# MSP430FR5739.net
KiCad netlist of a schematic drawn in Altium Designer
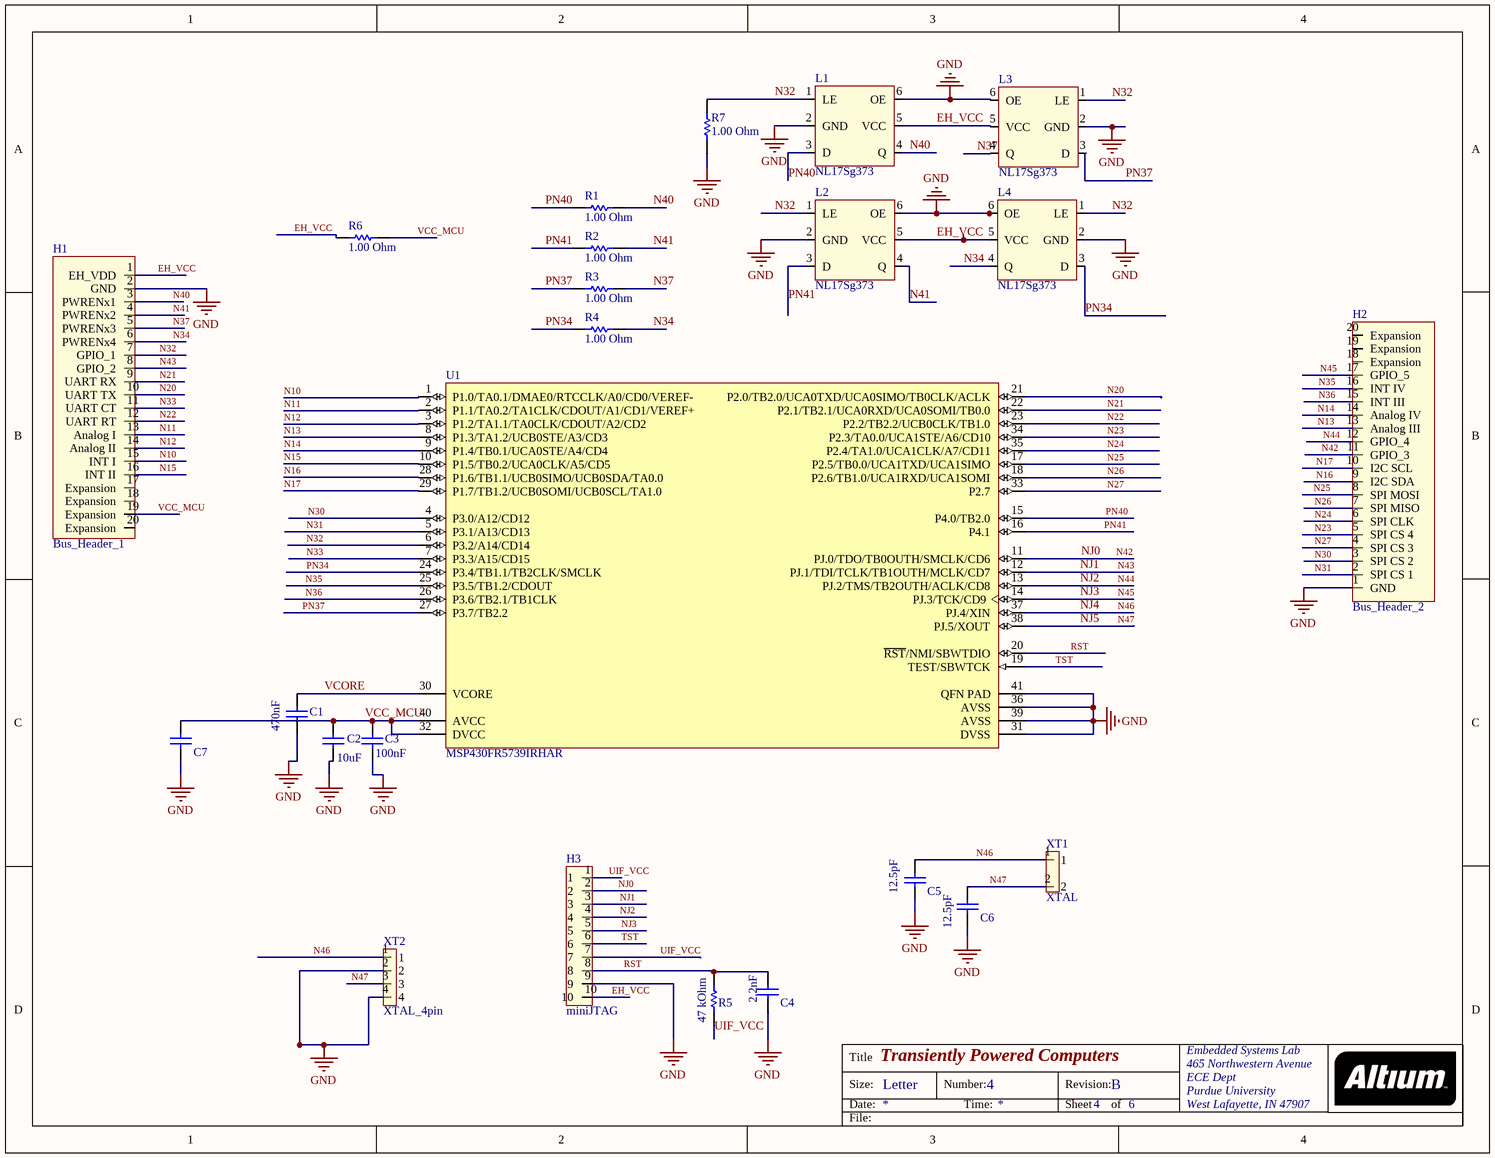
[diagram p0: MSP430FR5739.SchDoc]

(export (version "E")
  (design (tool "Eeschema 10.0.6"))
  (components
    (comp (ref "C1")
      (value "470nF")
      (footprint "CAPC0201(0603)33_N")
      (description "CAP 220nF 4V ±20% 0201 (0603 Metric) Thickness 0.33mm SMD")
      (fields (field (name "TOLERANCE") "±20%") (field (name "Comment") "CAP 220nF 4V 0201(0603)"))
      (libsource (lib "Altium Content Vault") (part "CAP"))
    )
    (comp (ref "C2")
      (value "10uF")
      (footprint "CAPC0402(1005)70_N")
      (description "CAP 10uF 4V ±20% 0402 (1005 Metric) Thickness 0.7mm SMD")
      (fields (field (name "TOLERANCE") "±20%") (field (name "Comment") "CAP 4.7uF 4V 0402(1005)"))
      (libsource (lib "Altium Content Vault") (part "CAP"))
    )
    (comp (ref "C3")
      (value "100nF")
      (footprint "CAPC0201(0603)33_M")
      (description "CAP 100nF 4V ±10% 0201 (0603 Metric) Thickness 0.33mm SMD")
      (fields (field (name "TOLERANCE") "±10%") (field (name "Comment") "CAP 100nF 4V 0201(0603)"))
      (libsource (lib "Altium Content Vault") (part "CMP-1033-00657-1"))
    )
    (comp (ref "C4")
      (value "2.2nF")
      (footprint "CAPC0402(1005)60_M")
      (description "CAP 2.2uF 4V ±20% 0402 (1005 Metric) Thickness 0.6mm SMD")
      (fields (field (name "TOLERANCE") "±20%") (field (name "Comment") "CAP 2.2uF 4V 0402(1005)"))
      (libsource (lib "Altium Content Vault") (part "CMP-1034-02124-1"))
    )
    (comp (ref "C5")
      (value "12.5pF")
      (footprint "CAPC0402(1005)60_N")
      (description "CAP 470nF 4V ±10% 0402 (1005 Metric) Thickness 0.6mm SMD")
      (fields (field (name "TOLERANCE") "±10%") (field (name "Comment") "CAP 470nF 4V 0402(1005)"))
      (libsource (lib "Altium Content Vault") (part "CMP-1034-02101-1"))
    )
    (comp (ref "C6")
      (value "12.5pF")
      (footprint "CAPC0402(1005)60_N")
      (description "CAP 470nF 4V ±10% 0402 (1005 Metric) Thickness 0.6mm SMD")
      (fields (field (name "TOLERANCE") "±10%") (field (name "Comment") "CAP 470nF 4V 0402(1005)"))
      (libsource (lib "Altium Content Vault") (part "CMP-1034-02101-1"))
    )
    (comp (ref "C7")
      (value "CAP 0.5pF 10V 0805(2012)")
      (footprint "CAPC0805(2012)75_N")
      (description "CAP 0.5pF 10V ±0.1pF 0805 (2012 Metric) Thickness 0.75mm SMD")
      (fields (field (name "TOLERANCE") "±0.1pF"))
      (libsource (lib "Altium Content Vault") (part "CMP-1036-00001-1"))
    )
    (comp (ref "H1")
      (value "Bus_Header_1")
      (footprint "Male Single row 20 pin header")
      (libsource (lib "Basic_components_hrishi") (part "Bus_Header_1"))
    )
    (comp (ref "H2")
      (value "Bus_Header_2")
      (footprint "Male Single row 20 pin header")
      (libsource (lib "Basic_components_hrishi") (part "Bus_Header_2"))
    )
    (comp (ref "H3")
      (value "miniJTAG")
      (footprint "SMT10pin_micro")
      (libsource (lib "Basic_components_hrishi") (part "miniJTAG"))
    )
    (comp (ref "L1")
      (value "NL17Sg373")
      (footprint "SOT65P210X110-6N")
      (libsource (lib "") (part "NL17Sg373_1"))
    )
    (comp (ref "L2")
      (value "NL17Sg373")
      (footprint "SOT65P210X110-6N")
      (libsource (lib "") (part "NL17Sg373_1"))
    )
    (comp (ref "L3")
      (value "NL17Sg373")
      (footprint "SOT65P210X110-6N")
      (libsource (lib "Basic_components_hrishi") (part "NL17Sg373"))
    )
    (comp (ref "L4")
      (value "NL17Sg373")
      (footprint "SOT65P210X110-6N")
      (libsource (lib "Basic_components_hrishi") (part "NL17Sg373"))
    )
    (comp (ref "R1")
      (value "1.00 Ohm")
      (footprint "RESC0402(1005)_N")
      (description "1R 0.063W 5% 0402 (1005 Metric)  SMD")
      (fields (field (name "POWER") "0.063 W") (field (name "TOLERANCE") "5 %"))
      (libsource (lib "Altium Content Vault") (part "CMP-1011-00002-1"))
    )
    (comp (ref "R2")
      (value "1.00 Ohm")
      (footprint "RESC0402(1005)_N")
      (description "1R 0.063W 5% 0402 (1005 Metric)  SMD")
      (fields (field (name "POWER") "0.063 W") (field (name "TOLERANCE") "5 %"))
      (libsource (lib "Altium Content Vault") (part "CMP-1011-00002-1"))
    )
    (comp (ref "R3")
      (value "1.00 Ohm")
      (footprint "RESC0402(1005)_N")
      (description "1R 0.063W 5% 0402 (1005 Metric)  SMD")
      (fields (field (name "POWER") "0.063 W") (field (name "TOLERANCE") "5 %"))
      (libsource (lib "Altium Content Vault") (part "CMP-1011-00002-1"))
    )
    (comp (ref "R4")
      (value "1.00 Ohm")
      (footprint "RESC0402(1005)_N")
      (description "1R 0.063W 5% 0402 (1005 Metric)  SMD")
      (fields (field (name "POWER") "0.063 W") (field (name "TOLERANCE") "5 %"))
      (libsource (lib "Altium Content Vault") (part "CMP-1011-00002-1"))
    )
    (comp (ref "R5")
      (value "47 kOhm")
      (footprint "RESC0402(1005)_M")
      (description "47K 0.063W 5% 0402 (1005 Metric)  SMD")
      (fields (field (name "TOLERANCE") "5 %") (field (name "POWER") "0.063 W"))
      (libsource (lib "Altium Content Vault") (part "CMP-1011-00114-1"))
    )
    (comp (ref "R6")
      (value "1.00 Ohm")
      (footprint "RESC0402(1005)_N")
      (description "1R 0.063W 5% 0402 (1005 Metric)  SMD")
      (fields (field (name "POWER") "0.063 W") (field (name "TOLERANCE") "5 %"))
      (libsource (lib "Altium Content Vault") (part "CMP-1011-00002-1"))
    )
    (comp (ref "R7")
      (value "1.00 Ohm")
      (footprint "RESC0402(1005)_N")
      (description "1R 0.063W 5% 0402 (1005 Metric)  SMD")
      (fields (field (name "POWER") "0.063 W") (field (name "TOLERANCE") "5 %"))
      (libsource (lib "Altium Content Vault") (part "CMP-1011-00002-1"))
    )
    (comp (ref "U1")
      (value "MSP430FR5739IRHAR")
      (footprint "Via_modified_TI-RHA40-2900X2900TP_N")
      (fields (field (name "MANUFACTURER") "Texas Instruments"))
      (libsource (lib "Altium Content Vault") (part "CMP-0365-01094-1"))
    )
    (comp (ref "XT1")
      (value "XTAL")
      (footprint "Crystal_32")
      (libsource (lib "Basic_components_hrishi") (part "XTAL"))
    )
    (comp (ref "XT2")
      (value "XTAL_4pin")
      (footprint "CRYSTAL_MHZ")
      (libsource (lib "Basic_components_hrishi") (part "XTAL_4pin"))
    )
  )
  (nets
    (net (code "1") (name "/EH_VCC") (class "Default")
      (node (ref "H1") (pin "1") (pinfunction "EH_VDD_1") (pintype "passive"))
      (node (ref "H3") (pin "10") (pinfunction "10_10") (pintype "passive"))
      (node (ref "L1") (pin "5") (pinfunction "VCC_5") (pintype "passive"))
      (node (ref "L2") (pin "5") (pinfunction "VCC_5") (pintype "passive"))
      (node (ref "L3") (pin "5") (pinfunction "VCC_5") (pintype "passive"))
      (node (ref "L4") (pin "5") (pinfunction "VCC_5") (pintype "passive"))
      (node (ref "R6") (pin "2") (pinfunction "2_2") (pintype "passive"))
    )
    (net (code "2") (name "/N10") (class "Default")
      (node (ref "H1") (pin "15") (pinfunction "INT_I_15") (pintype "passive"))
      (node (ref "U1") (pin "1") (pinfunction "P1.0/TA0.1/DMAE0/RTCCLK/A0/CD0/VEREF-_1") (pintype "bidirectional"))
    )
    (net (code "3") (name "/N11") (class "Default")
      (node (ref "H1") (pin "13") (pinfunction "Analog_I_13") (pintype "passive"))
      (node (ref "U1") (pin "2") (pinfunction "P1.1/TA0.2/TA1CLK/CDOUT/A1/CD1/VEREF+_2") (pintype "bidirectional"))
    )
    (net (code "4") (name "/N12") (class "Default")
      (node (ref "H1") (pin "14") (pinfunction "Analog_II_14") (pintype "passive"))
      (node (ref "U1") (pin "3") (pinfunction "P1.2/TA1.1/TA0CLK/CDOUT/A2/CD2_3") (pintype "bidirectional"))
    )
    (net (code "5") (name "/N13") (class "Default")
      (node (ref "H2") (pin "13") (pinfunction "Analog_III_13") (pintype "passive"))
      (node (ref "U1") (pin "8") (pinfunction "P1.3/TA1.2/UCB0STE/A3/CD3_8") (pintype "bidirectional"))
    )
    (net (code "6") (name "/N14") (class "Default")
      (node (ref "H2") (pin "14") (pinfunction "Analog_IV_14") (pintype "passive"))
      (node (ref "U1") (pin "9") (pinfunction "P1.4/TB0.1/UCA0STE/A4/CD4_9") (pintype "bidirectional"))
    )
    (net (code "7") (name "/N15") (class "Default")
      (node (ref "H1") (pin "16") (pinfunction "INT_II_16") (pintype "passive"))
      (node (ref "U1") (pin "10") (pinfunction "P1.5/TB0.2/UCA0CLK/A5/CD5_10") (pintype "bidirectional"))
    )
    (net (code "8") (name "/N16") (class "Default")
      (node (ref "H2") (pin "9") (pinfunction "I2C_SDA_9") (pintype "passive"))
      (node (ref "U1") (pin "28") (pinfunction "P1.6/TB1.1/UCB0SIMO/UCB0SDA/TA0.0_28") (pintype "bidirectional"))
    )
    (net (code "9") (name "/N17") (class "Default")
      (node (ref "H2") (pin "10") (pinfunction "I2C_SCL_10") (pintype "passive"))
      (node (ref "U1") (pin "29") (pinfunction "P1.7/TB1.2/UCB0SOMI/UCB0SCL/TA1.0_29") (pintype "bidirectional"))
    )
    (net (code "10") (name "/N20") (class "Default")
      (node (ref "H1") (pin "10") (pinfunction "UART_TX_10") (pintype "passive"))
      (node (ref "U1") (pin "21") (pinfunction "P2.0/TB2.0/UCA0TXD/UCA0SIMO/TB0CLK/ACLK_21") (pintype "bidirectional"))
    )
    (net (code "11") (name "/N21") (class "Default")
      (node (ref "H1") (pin "9") (pinfunction "UART_RX_9") (pintype "passive"))
      (node (ref "U1") (pin "22") (pinfunction "P2.1/TB2.1/UCA0RXD/UCA0SOMI/TB0.0_22") (pintype "bidirectional"))
    )
    (net (code "12") (name "/N22") (class "Default")
      (node (ref "H1") (pin "12") (pinfunction "UART_RT_12") (pintype "passive"))
      (node (ref "U1") (pin "23") (pinfunction "P2.2/TB2.2/UCB0CLK/TB1.0_23") (pintype "bidirectional"))
    )
    (net (code "13") (name "/N23") (class "Default")
      (node (ref "H2") (pin "5") (pinfunction "SPI_CS_4_5") (pintype "passive"))
      (node (ref "U1") (pin "34") (pinfunction "P2.3/TA0.0/UCA1STE/A6/CD10_34") (pintype "bidirectional"))
    )
    (net (code "14") (name "/N24") (class "Default")
      (node (ref "H2") (pin "6") (pinfunction "SPI_CLK_6") (pintype "passive"))
      (node (ref "U1") (pin "35") (pinfunction "P2.4/TA1.0/UCA1CLK/A7/CD11_35") (pintype "bidirectional"))
    )
    (net (code "15") (name "/N25") (class "Default")
      (node (ref "H2") (pin "8") (pinfunction "SPI_MOSI_8") (pintype "passive"))
      (node (ref "U1") (pin "17") (pinfunction "P2.5/TB0.0/UCA1TXD/UCA1SIMO_17") (pintype "bidirectional"))
    )
    (net (code "16") (name "/N26") (class "Default")
      (node (ref "H2") (pin "7") (pinfunction "SPI_MISO_7") (pintype "passive"))
      (node (ref "U1") (pin "18") (pinfunction "P2.6/TB1.0/UCA1RXD/UCA1SOMI_18") (pintype "bidirectional"))
    )
    (net (code "17") (name "/N27") (class "Default")
      (node (ref "H2") (pin "4") (pinfunction "SPI_CS_3_4") (pintype "passive"))
      (node (ref "U1") (pin "33") (pinfunction "P2.7_33") (pintype "bidirectional"))
    )
    (net (code "18") (name "/N30") (class "Default")
      (node (ref "H2") (pin "3") (pinfunction "SPI_CS_2_3") (pintype "passive"))
      (node (ref "U1") (pin "4") (pinfunction "P3.0/A12/CD12_4") (pintype "bidirectional"))
    )
    (net (code "19") (name "/N31") (class "Default")
      (node (ref "H2") (pin "2") (pinfunction "SPI_CS_1_2") (pintype "passive"))
      (node (ref "U1") (pin "5") (pinfunction "P3.1/A13/CD13_5") (pintype "bidirectional"))
    )
    (net (code "20") (name "/N32") (class "Default")
      (node (ref "H1") (pin "7") (pinfunction "GPIO_1_7") (pintype "passive"))
      (node (ref "L1") (pin "1") (pinfunction "LE_1") (pintype "passive"))
      (node (ref "L2") (pin "1") (pinfunction "LE_1") (pintype "passive"))
      (node (ref "L3") (pin "1") (pinfunction "LE_1") (pintype "passive"))
      (node (ref "L4") (pin "1") (pinfunction "LE_1") (pintype "passive"))
      (node (ref "R7") (pin "1") (pinfunction "1_1") (pintype "passive"))
      (node (ref "U1") (pin "6") (pinfunction "P3.2/A14/CD14_6") (pintype "bidirectional"))
    )
    (net (code "21") (name "/N33") (class "Default")
      (node (ref "H1") (pin "11") (pinfunction "UART_CT_11") (pintype "passive"))
      (node (ref "U1") (pin "7") (pinfunction "P3.3/A15/CD15_7") (pintype "bidirectional"))
    )
    (net (code "22") (name "/N34") (class "Default")
      (node (ref "H1") (pin "6") (pinfunction "PWRENx4_6") (pintype "passive"))
      (node (ref "L4") (pin "4") (pinfunction "Q_4") (pintype "passive"))
      (node (ref "R4") (pin "1") (pinfunction "1_1") (pintype "passive"))
    )
    (net (code "23") (name "/N35") (class "Default")
      (node (ref "H2") (pin "16") (pinfunction "INT_IV_16") (pintype "passive"))
      (node (ref "U1") (pin "25") (pinfunction "P3.5/TB1.2/CDOUT_25") (pintype "bidirectional"))
    )
    (net (code "24") (name "/N36") (class "Default")
      (node (ref "H2") (pin "15") (pinfunction "INT_III_15") (pintype "passive"))
      (node (ref "U1") (pin "26") (pinfunction "P3.6/TB2.1/TB1CLK_26") (pintype "bidirectional"))
    )
    (net (code "25") (name "/N37") (class "Default")
      (node (ref "H1") (pin "5") (pinfunction "PWRENx3_5") (pintype "passive"))
      (node (ref "L3") (pin "4") (pinfunction "Q_4") (pintype "passive"))
      (node (ref "R3") (pin "1") (pinfunction "1_1") (pintype "passive"))
    )
    (net (code "26") (name "/N40") (class "Default")
      (node (ref "H1") (pin "3") (pinfunction "PWRENx1_3") (pintype "passive"))
      (node (ref "L1") (pin "4") (pinfunction "Q_4") (pintype "passive"))
      (node (ref "R1") (pin "1") (pinfunction "1_1") (pintype "passive"))
    )
    (net (code "27") (name "/N41") (class "Default")
      (node (ref "H1") (pin "4") (pinfunction "PWRENx2_4") (pintype "passive"))
      (node (ref "L2") (pin "4") (pinfunction "Q_4") (pintype "passive"))
      (node (ref "R2") (pin "1") (pinfunction "1_1") (pintype "passive"))
    )
    (net (code "28") (name "/N42") (class "Default")
      (node (ref "H2") (pin "11") (pinfunction "GPIO_3_11") (pintype "passive"))
      (node (ref "H3") (pin "2") (pinfunction "2_2") (pintype "passive"))
      (node (ref "U1") (pin "11") (pinfunction "PJ.0/TDO/TB0OUTH/SMCLK/CD6_11") (pintype "bidirectional"))
    )
    (net (code "29") (name "/N43") (class "Default")
      (node (ref "H1") (pin "8") (pinfunction "GPIO_2_8") (pintype "passive"))
      (node (ref "H3") (pin "3") (pinfunction "3_3") (pintype "passive"))
      (node (ref "U1") (pin "12") (pinfunction "PJ.1/TDI/TCLK/TB1OUTH/MCLK/CD7_12") (pintype "bidirectional"))
    )
    (net (code "30") (name "/N44") (class "Default")
      (node (ref "H2") (pin "12") (pinfunction "GPIO_4_12") (pintype "passive"))
      (node (ref "H3") (pin "4") (pinfunction "4_4") (pintype "passive"))
      (node (ref "U1") (pin "13") (pinfunction "PJ.2/TMS/TB2OUTH/ACLK/CD8_13") (pintype "bidirectional"))
    )
    (net (code "31") (name "/N45") (class "Default")
      (node (ref "H2") (pin "17") (pinfunction "GPIO_5_17") (pintype "passive"))
      (node (ref "H3") (pin "5") (pinfunction "5_5") (pintype "passive"))
      (node (ref "U1") (pin "14") (pinfunction "PJ.3/TCK/CD9_14") (pintype "bidirectional"))
    )
    (net (code "32") (name "/N46") (class "Default")
      (node (ref "C5") (pin "2") (pinfunction "2_2") (pintype "passive"))
      (node (ref "U1") (pin "37") (pinfunction "PJ.4/XIN_37") (pintype "bidirectional"))
      (node (ref "XT1") (pin "1") (pinfunction "1_1") (pintype "passive"))
      (node (ref "XT2") (pin "1") (pinfunction "1_1") (pintype "passive"))
    )
    (net (code "33") (name "/N47") (class "Default")
      (node (ref "C6") (pin "2") (pinfunction "2_2") (pintype "passive"))
      (node (ref "U1") (pin "38") (pinfunction "PJ.5/XOUT_38") (pintype "bidirectional"))
      (node (ref "XT1") (pin "2") (pinfunction "2_2") (pintype "passive"))
      (node (ref "XT2") (pin "3") (pinfunction "3_3") (pintype "passive"))
    )
    (net (code "34") (name "/PN34") (class "Default")
      (node (ref "L4") (pin "3") (pinfunction "D_3") (pintype "passive"))
      (node (ref "R4") (pin "2") (pinfunction "2_2") (pintype "passive"))
      (node (ref "U1") (pin "24") (pinfunction "P3.4/TB1.1/TB2CLK/SMCLK_24") (pintype "bidirectional"))
    )
    (net (code "35") (name "/PN37") (class "Default")
      (node (ref "L3") (pin "3") (pinfunction "D_3") (pintype "passive"))
      (node (ref "R3") (pin "2") (pinfunction "2_2") (pintype "passive"))
      (node (ref "U1") (pin "27") (pinfunction "P3.7/TB2.2_27") (pintype "bidirectional"))
    )
    (net (code "36") (name "/PN40") (class "Default")
      (node (ref "L1") (pin "3") (pinfunction "D_3") (pintype "passive"))
      (node (ref "R1") (pin "2") (pinfunction "2_2") (pintype "passive"))
      (node (ref "U1") (pin "15") (pinfunction "P4.0/TB2.0_15") (pintype "bidirectional"))
    )
    (net (code "37") (name "/PN41") (class "Default")
      (node (ref "L2") (pin "3") (pinfunction "D_3") (pintype "passive"))
      (node (ref "R2") (pin "2") (pinfunction "2_2") (pintype "passive"))
      (node (ref "U1") (pin "16") (pinfunction "P4.1_16") (pintype "bidirectional"))
    )
    (net (code "38") (name "/RST") (class "Default")
      (node (ref "C4") (pin "2") (pinfunction "2_2") (pintype "passive"))
      (node (ref "H3") (pin "8") (pinfunction "8_8") (pintype "passive"))
      (node (ref "R5") (pin "2") (pinfunction "2_2") (pintype "passive"))
      (node (ref "U1") (pin "20") (pinfunction "~{RST}/NMI/SBWTDIO_20") (pintype "bidirectional"))
    )
    (net (code "39") (name "/TST") (class "Default")
      (node (ref "H3") (pin "6") (pinfunction "6_6") (pintype "passive"))
      (node (ref "U1") (pin "19") (pinfunction "TEST/SBWTCK_19") (pintype "input"))
    )
    (net (code "40") (name "/UIF_VCC") (class "Default")
      (node (ref "H3") (pin "1") (pinfunction "1_1") (pintype "passive"))
      (node (ref "H3") (pin "7") (pinfunction "7_7") (pintype "passive"))
      (node (ref "R5") (pin "1") (pinfunction "1_1") (pintype "passive"))
    )
    (net (code "41") (name "/VCC_MCU") (class "Default")
      (node (ref "C2") (pin "2") (pinfunction "2_2") (pintype "passive"))
      (node (ref "C3") (pin "2") (pinfunction "2_2") (pintype "passive"))
      (node (ref "C7") (pin "2") (pinfunction "2_2") (pintype "passive"))
      (node (ref "H1") (pin "19") (pinfunction "Expansion_19") (pintype "passive"))
      (node (ref "R6") (pin "1") (pinfunction "1_1") (pintype "passive"))
      (node (ref "U1") (pin "32") (pinfunction "DVCC_32") (pintype "power_in"))
      (node (ref "U1") (pin "40") (pinfunction "AVCC_40") (pintype "power_in"))
    )
    (net (code "42") (name "/VCORE") (class "Default")
      (node (ref "C1") (pin "2") (pinfunction "2_2") (pintype "passive"))
      (node (ref "U1") (pin "30") (pinfunction "VCORE_30") (pintype "passive"))
    )
    (net (code "43") (name "GND") (class "Default")
      (node (ref "C1") (pin "1") (pinfunction "1_1") (pintype "passive"))
      (node (ref "C2") (pin "1") (pinfunction "1_1") (pintype "passive"))
      (node (ref "C3") (pin "1") (pinfunction "1_1") (pintype "passive"))
      (node (ref "C4") (pin "1") (pinfunction "1_1") (pintype "passive"))
      (node (ref "C5") (pin "1") (pinfunction "1_1") (pintype "passive"))
      (node (ref "C6") (pin "1") (pinfunction "1_1") (pintype "passive"))
      (node (ref "C7") (pin "1") (pinfunction "1_1") (pintype "passive"))
      (node (ref "H1") (pin "2") (pinfunction "GND_2") (pintype "passive"))
      (node (ref "H2") (pin "1") (pinfunction "GND_1") (pintype "passive"))
      (node (ref "H3") (pin "9") (pinfunction "9_9") (pintype "passive"))
      (node (ref "L1") (pin "2") (pinfunction "GND_2") (pintype "passive"))
      (node (ref "L1") (pin "6") (pinfunction "OE_6") (pintype "passive"))
      (node (ref "L2") (pin "2") (pinfunction "GND_2") (pintype "passive"))
      (node (ref "L2") (pin "6") (pinfunction "OE_6") (pintype "passive"))
      (node (ref "L3") (pin "2") (pinfunction "GND_2") (pintype "passive"))
      (node (ref "L3") (pin "6") (pinfunction "OE_6") (pintype "passive"))
      (node (ref "L4") (pin "2") (pinfunction "GND_2") (pintype "passive"))
      (node (ref "L4") (pin "6") (pinfunction "OE_6") (pintype "passive"))
      (node (ref "R7") (pin "2") (pinfunction "2_2") (pintype "passive"))
      (node (ref "U1") (pin "31") (pinfunction "DVSS_31") (pintype "power_in"))
      (node (ref "U1") (pin "36") (pinfunction "AVSS_36") (pintype "power_in"))
      (node (ref "U1") (pin "39") (pinfunction "AVSS_39") (pintype "power_in"))
      (node (ref "U1") (pin "41") (pinfunction "QFN_PAD_41") (pintype "power_in"))
      (node (ref "XT2") (pin "2") (pinfunction "2_2") (pintype "passive"))
      (node (ref "XT2") (pin "4") (pinfunction "4_4") (pintype "passive"))
    )
    (net (code "44") (name "unconnected-(H1-Expansion-Pad17)") (class "Default")
      (node (ref "H1") (pin "17") (pinfunction "Expansion_17") (pintype "passive"))
    )
    (net (code "45") (name "unconnected-(H1-Expansion-Pad18)") (class "Default")
      (node (ref "H1") (pin "18") (pinfunction "Expansion_18") (pintype "passive"))
    )
    (net (code "46") (name "unconnected-(H1-Expansion-Pad20)") (class "Default")
      (node (ref "H1") (pin "20") (pinfunction "Expansion_20") (pintype "passive"))
    )
    (net (code "47") (name "unconnected-(H2-Expansion-Pad18)") (class "Default")
      (node (ref "H2") (pin "18") (pinfunction "Expansion_18") (pintype "passive"))
    )
    (net (code "48") (name "unconnected-(H2-Expansion-Pad19)") (class "Default")
      (node (ref "H2") (pin "19") (pinfunction "Expansion_19") (pintype "passive"))
    )
    (net (code "49") (name "unconnected-(H2-Expansion-Pad20)") (class "Default")
      (node (ref "H2") (pin "20") (pinfunction "Expansion_20") (pintype "passive"))
    )
  )
)
